# smartStaircaseLighting.net
KiCad netlist of a schematic drawn in Altium Designer
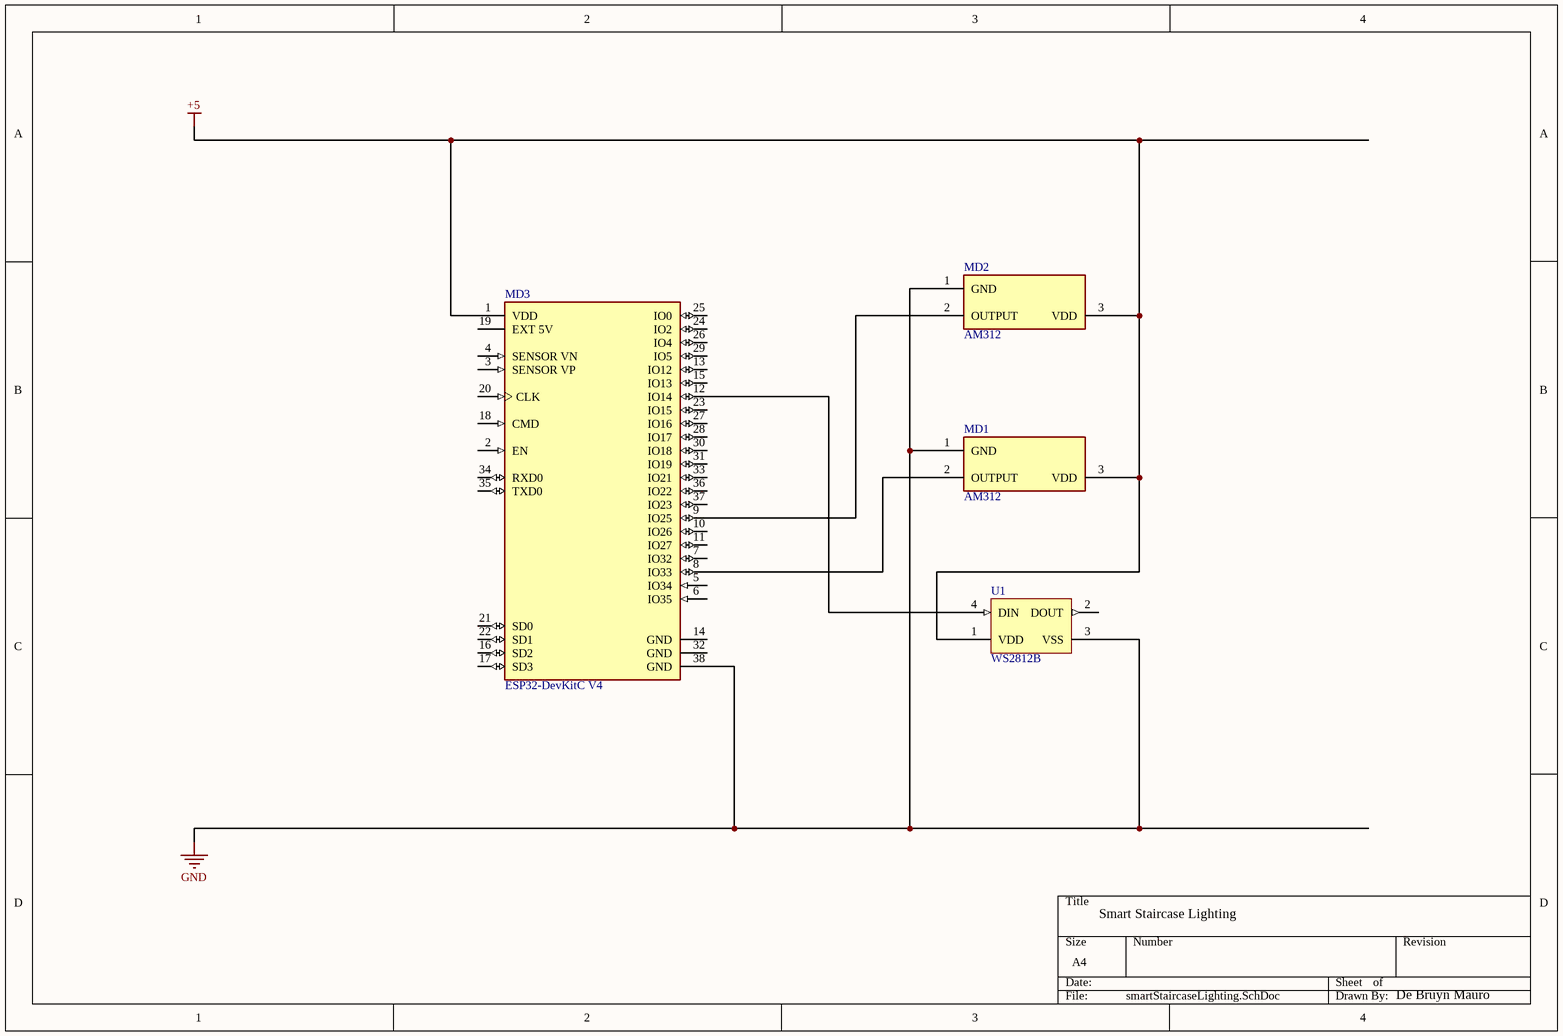
[diagram p0: smartStaircaseLighting.SchDoc]

(export (version "E")
  (design (tool "Eeschema 10.0.6"))
  (components
    (comp (ref "MD1")
      (value "AM312")
      (footprint "FP-EKMC1603111-MFG")
      (description "SENSOR MOTION PIR")
      (fields
        (field (name "MANUFACTURER") "Panasonic Electric Works")
        (field (name "OCTOPART") "https://octopart.com/ekmc1603111-panasonic-19688870")
      )
      (libsource (lib "Altium Content Vault") (part "a4f69fc217becd3c0d007a4ac4979f9"))
    )
    (comp (ref "MD2")
      (value "AM312")
      (footprint "FP-EKMC1603111-MFG")
      (description "SENSOR MOTION PIR")
      (fields
        (field (name "MANUFACTURER") "Panasonic Electric Works")
        (field (name "OCTOPART") "https://octopart.com/ekmc1603111-panasonic-19688870")
      )
      (libsource (lib "Altium Content Vault") (part "a4f69fc217becd3c0d007a4ac4979f9"))
    )
    (comp (ref "MD3")
      (value "ESP32-DevKitC V4")
      (footprint "FP-ESP32-DevKitC_V4-MFG")
      (description "WiFi Development Tools (802.11) ESP32 General Development Kit, ESP32-WROOM-32 on the board")
      (fields
        (field (name "OCTOPART") "https://octopart.com/esp32-devkitc+v4-espressif+systems-107467262")
        (field (name "MANUFACTURER") "Espressif")
      )
      (libsource (lib "Altium Content Vault") (part "5ae961a1152c677524a60dea72d22f3"))
    )
    (comp (ref "U1")
      (value "WS2812B")
      (footprint "ADA-RGB-1655_V")
      (description "Adressable LED strip WS2812B")
      (fields (field (name "MANUFACTURER") "Adafruit-Industries-LLC"))
      (libsource (lib "Altium Content Vault") (part "ADA-RGB-1655-4"))
    )
  )
  (nets
    (net (code "1") (name "+5") (class "Default")
      (node (ref "MD1") (pin "3") (pinfunction "VDD_3") (pintype "power_in"))
      (node (ref "MD2") (pin "3") (pinfunction "VDD_3") (pintype "power_in"))
      (node (ref "MD3") (pin "1") (pinfunction "VDD_1") (pintype "power_in"))
      (node (ref "U1") (pin "1") (pinfunction "VDD_1") (pintype "power_in"))
    )
    (net (code "2") (name "GND") (class "Default")
      (node (ref "MD1") (pin "1") (pinfunction "GND_1") (pintype "power_in"))
      (node (ref "MD2") (pin "1") (pinfunction "GND_1") (pintype "power_in"))
      (node (ref "MD3") (pin "38") (pinfunction "GND_38") (pintype "power_in"))
      (node (ref "U1") (pin "3") (pinfunction "VSS_3") (pintype "power_in"))
    )
    (net (code "3") (name "Net-(MD1-OUTPUT)") (class "Default")
      (node (ref "MD1") (pin "2") (pinfunction "OUTPUT_2") (pintype "open_collector"))
      (node (ref "MD3") (pin "8") (pinfunction "IO33_8") (pintype "bidirectional"))
    )
    (net (code "4") (name "Net-(MD2-OUTPUT)") (class "Default")
      (node (ref "MD2") (pin "2") (pinfunction "OUTPUT_2") (pintype "open_collector"))
      (node (ref "MD3") (pin "9") (pinfunction "IO25_9") (pintype "bidirectional"))
    )
    (net (code "5") (name "Net-(MD3-IO14)") (class "Default")
      (node (ref "MD3") (pin "12") (pinfunction "IO14_12") (pintype "bidirectional"))
      (node (ref "U1") (pin "4") (pinfunction "DIN_4") (pintype "input"))
    )
    (net (code "6") (name "unconnected-(MD3-CLK-Pad20)") (class "Default")
      (node (ref "MD3") (pin "20") (pinfunction "CLK_20") (pintype "input"))
    )
    (net (code "7") (name "unconnected-(MD3-CMD-Pad18)") (class "Default")
      (node (ref "MD3") (pin "18") (pinfunction "CMD_18") (pintype "input"))
    )
    (net (code "8") (name "unconnected-(MD3-EN-Pad2)") (class "Default")
      (node (ref "MD3") (pin "2") (pinfunction "EN_2") (pintype "input"))
    )
    (net (code "9") (name "unconnected-(MD3-EXT_5V-Pad19)") (class "Default")
      (node (ref "MD3") (pin "19") (pinfunction "EXT_5V_19") (pintype "power_in"))
    )
    (net (code "10") (name "unconnected-(MD3-GND-Pad14)") (class "Default")
      (node (ref "MD3") (pin "14") (pinfunction "GND_14") (pintype "power_in"))
    )
    (net (code "11") (name "unconnected-(MD3-GND-Pad32)") (class "Default")
      (node (ref "MD3") (pin "32") (pinfunction "GND_32") (pintype "power_in"))
    )
    (net (code "12") (name "unconnected-(MD3-IO0-Pad25)") (class "Default")
      (node (ref "MD3") (pin "25") (pinfunction "IO0_25") (pintype "bidirectional"))
    )
    (net (code "13") (name "unconnected-(MD3-IO2-Pad24)") (class "Default")
      (node (ref "MD3") (pin "24") (pinfunction "IO2_24") (pintype "bidirectional"))
    )
    (net (code "14") (name "unconnected-(MD3-IO4-Pad26)") (class "Default")
      (node (ref "MD3") (pin "26") (pinfunction "IO4_26") (pintype "bidirectional"))
    )
    (net (code "15") (name "unconnected-(MD3-IO5-Pad29)") (class "Default")
      (node (ref "MD3") (pin "29") (pinfunction "IO5_29") (pintype "bidirectional"))
    )
    (net (code "16") (name "unconnected-(MD3-IO12-Pad13)") (class "Default")
      (node (ref "MD3") (pin "13") (pinfunction "IO12_13") (pintype "bidirectional"))
    )
    (net (code "17") (name "unconnected-(MD3-IO13-Pad15)") (class "Default")
      (node (ref "MD3") (pin "15") (pinfunction "IO13_15") (pintype "bidirectional"))
    )
    (net (code "18") (name "unconnected-(MD3-IO15-Pad23)") (class "Default")
      (node (ref "MD3") (pin "23") (pinfunction "IO15_23") (pintype "bidirectional"))
    )
    (net (code "19") (name "unconnected-(MD3-IO16-Pad27)") (class "Default")
      (node (ref "MD3") (pin "27") (pinfunction "IO16_27") (pintype "bidirectional"))
    )
    (net (code "20") (name "unconnected-(MD3-IO17-Pad28)") (class "Default")
      (node (ref "MD3") (pin "28") (pinfunction "IO17_28") (pintype "bidirectional"))
    )
    (net (code "21") (name "unconnected-(MD3-IO18-Pad30)") (class "Default")
      (node (ref "MD3") (pin "30") (pinfunction "IO18_30") (pintype "bidirectional"))
    )
    (net (code "22") (name "unconnected-(MD3-IO19-Pad31)") (class "Default")
      (node (ref "MD3") (pin "31") (pinfunction "IO19_31") (pintype "bidirectional"))
    )
    (net (code "23") (name "unconnected-(MD3-IO21-Pad33)") (class "Default")
      (node (ref "MD3") (pin "33") (pinfunction "IO21_33") (pintype "bidirectional"))
    )
    (net (code "24") (name "unconnected-(MD3-IO22-Pad36)") (class "Default")
      (node (ref "MD3") (pin "36") (pinfunction "IO22_36") (pintype "bidirectional"))
    )
    (net (code "25") (name "unconnected-(MD3-IO23-Pad37)") (class "Default")
      (node (ref "MD3") (pin "37") (pinfunction "IO23_37") (pintype "bidirectional"))
    )
    (net (code "26") (name "unconnected-(MD3-IO26-Pad10)") (class "Default")
      (node (ref "MD3") (pin "10") (pinfunction "IO26_10") (pintype "bidirectional"))
    )
    (net (code "27") (name "unconnected-(MD3-IO27-Pad11)") (class "Default")
      (node (ref "MD3") (pin "11") (pinfunction "IO27_11") (pintype "bidirectional"))
    )
    (net (code "28") (name "unconnected-(MD3-IO32-Pad7)") (class "Default")
      (node (ref "MD3") (pin "7") (pinfunction "IO32_7") (pintype "bidirectional"))
    )
    (net (code "29") (name "unconnected-(MD3-IO34-Pad5)") (class "Default")
      (node (ref "MD3") (pin "5") (pinfunction "IO34_5") (pintype "input"))
    )
    (net (code "30") (name "unconnected-(MD3-IO35-Pad6)") (class "Default")
      (node (ref "MD3") (pin "6") (pinfunction "IO35_6") (pintype "input"))
    )
    (net (code "31") (name "unconnected-(MD3-RXD0-Pad34)") (class "Default")
      (node (ref "MD3") (pin "34") (pinfunction "RXD0_34") (pintype "bidirectional"))
    )
    (net (code "32") (name "unconnected-(MD3-SD0-Pad21)") (class "Default")
      (node (ref "MD3") (pin "21") (pinfunction "SD0_21") (pintype "bidirectional"))
    )
    (net (code "33") (name "unconnected-(MD3-SD1-Pad22)") (class "Default")
      (node (ref "MD3") (pin "22") (pinfunction "SD1_22") (pintype "bidirectional"))
    )
    (net (code "34") (name "unconnected-(MD3-SD2-Pad16)") (class "Default")
      (node (ref "MD3") (pin "16") (pinfunction "SD2_16") (pintype "bidirectional"))
    )
    (net (code "35") (name "unconnected-(MD3-SD3-Pad17)") (class "Default")
      (node (ref "MD3") (pin "17") (pinfunction "SD3_17") (pintype "bidirectional"))
    )
    (net (code "36") (name "unconnected-(MD3-SENSOR_VN-Pad4)") (class "Default")
      (node (ref "MD3") (pin "4") (pinfunction "SENSOR_VN_4") (pintype "input"))
    )
    (net (code "37") (name "unconnected-(MD3-SENSOR_VP-Pad3)") (class "Default")
      (node (ref "MD3") (pin "3") (pinfunction "SENSOR_VP_3") (pintype "input"))
    )
    (net (code "38") (name "unconnected-(MD3-TXD0-Pad35)") (class "Default")
      (node (ref "MD3") (pin "35") (pinfunction "TXD0_35") (pintype "bidirectional"))
    )
    (net (code "39") (name "unconnected-(U1-DOUT-Pad2)") (class "Default")
      (node (ref "U1") (pin "2") (pinfunction "DOUT_2") (pintype "output"))
    )
  )
)
